# Nixie_Driver.net
KiCad netlist of a schematic drawn in EAGLE
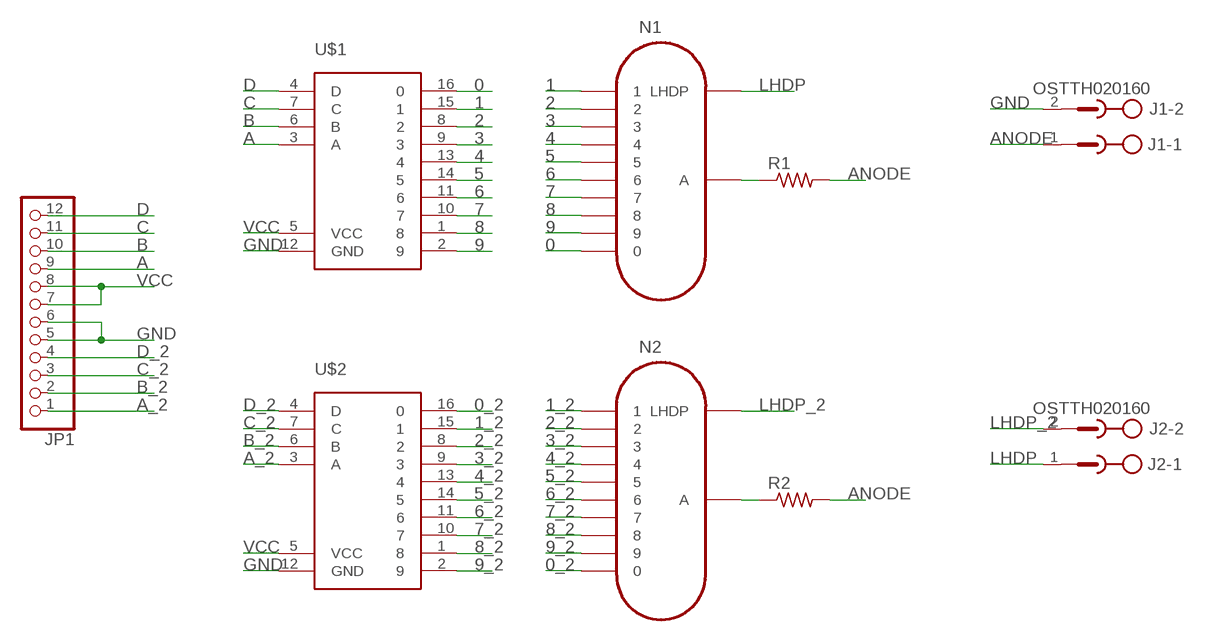
[diagram p0: schematic, sheet 1]

(export (version "E")
  (design (tool "Eeschema 10.0.6"))
  (components
    (comp (ref "J1")
      (value "OSTTH020160")
      (footprint "eagle-import:EDSTL130-02")
      (libsource (lib "eagle-import") (part "OSTTH020160"))
    )
    (comp (ref "J2")
      (value "OSTTH020160")
      (footprint "eagle-import:EDSTL130-02")
      (libsource (lib "eagle-import") (part "OSTTH020160"))
    )
    (comp (ref "JP1")
      (value "PINHD-1X12-CB")
      (footprint "eagle-import:1X12-CB")
      (libsource (lib "eagle-import") (part "PINHD-1X12-CB"))
    )
    (comp (ref "N1")
      (value "IN-12B")
      (footprint "eagle-import:IN-12")
      (libsource (lib "eagle-import") (part "IN-12B"))
    )
    (comp (ref "N2")
      (value "IN-12B")
      (footprint "eagle-import:IN-12")
      (libsource (lib "eagle-import") (part "IN-12B"))
    )
    (comp (ref "R1")
      (value "R-US_0204/7")
      (footprint "eagle-import:0204_7")
      (libsource (lib "eagle-import") (part "R-US_0204/7"))
    )
    (comp (ref "R2")
      (value "R-US_0204/7")
      (footprint "eagle-import:0204_7")
      (libsource (lib "eagle-import") (part "R-US_0204/7"))
    )
    (comp (ref "U$1")
      (value "K155ID1")
      (footprint "eagle-import:DIL16-KIT")
      (libsource (lib "eagle-import") (part "K155ID1"))
    )
    (comp (ref "U$2")
      (value "K155ID1")
      (footprint "eagle-import:DIL16-KIT")
      (libsource (lib "eagle-import") (part "K155ID1"))
    )
  )
  (nets
    (net (code "1") (name "/0") (class "Default")
      (node (ref "N1") (pin "0") (pinfunction "0_0") (pintype "bidirectional"))
      (node (ref "U$1") (pin "16") (pinfunction "0_16") (pintype "bidirectional"))
    )
    (net (code "2") (name "/0_2") (class "Default")
      (node (ref "N2") (pin "0") (pinfunction "0_0") (pintype "bidirectional"))
      (node (ref "U$2") (pin "16") (pinfunction "0_16") (pintype "bidirectional"))
    )
    (net (code "3") (name "/1") (class "Default")
      (node (ref "N1") (pin "1") (pinfunction "1_1") (pintype "bidirectional"))
      (node (ref "U$1") (pin "15") (pinfunction "1_15") (pintype "bidirectional"))
    )
    (net (code "4") (name "/1_2") (class "Default")
      (node (ref "N2") (pin "1") (pinfunction "1_1") (pintype "bidirectional"))
      (node (ref "U$2") (pin "15") (pinfunction "1_15") (pintype "bidirectional"))
    )
    (net (code "5") (name "/2") (class "Default")
      (node (ref "N1") (pin "2") (pinfunction "2_2") (pintype "bidirectional"))
      (node (ref "U$1") (pin "8") (pinfunction "2_8") (pintype "bidirectional"))
    )
    (net (code "6") (name "/2_2") (class "Default")
      (node (ref "N2") (pin "2") (pinfunction "2_2") (pintype "bidirectional"))
      (node (ref "U$2") (pin "8") (pinfunction "2_8") (pintype "bidirectional"))
    )
    (net (code "7") (name "/3") (class "Default")
      (node (ref "N1") (pin "3") (pinfunction "3_3") (pintype "bidirectional"))
      (node (ref "U$1") (pin "9") (pinfunction "3_9") (pintype "bidirectional"))
    )
    (net (code "8") (name "/3_2") (class "Default")
      (node (ref "N2") (pin "3") (pinfunction "3_3") (pintype "bidirectional"))
      (node (ref "U$2") (pin "9") (pinfunction "3_9") (pintype "bidirectional"))
    )
    (net (code "9") (name "/4") (class "Default")
      (node (ref "N1") (pin "4") (pinfunction "4_4") (pintype "bidirectional"))
      (node (ref "U$1") (pin "13") (pinfunction "4_13") (pintype "bidirectional"))
    )
    (net (code "10") (name "/4_2") (class "Default")
      (node (ref "N2") (pin "4") (pinfunction "4_4") (pintype "bidirectional"))
      (node (ref "U$2") (pin "13") (pinfunction "4_13") (pintype "bidirectional"))
    )
    (net (code "11") (name "/5") (class "Default")
      (node (ref "N1") (pin "5") (pinfunction "5_5") (pintype "bidirectional"))
      (node (ref "U$1") (pin "14") (pinfunction "5_14") (pintype "bidirectional"))
    )
    (net (code "12") (name "/5_2") (class "Default")
      (node (ref "N2") (pin "5") (pinfunction "5_5") (pintype "bidirectional"))
      (node (ref "U$2") (pin "14") (pinfunction "5_14") (pintype "bidirectional"))
    )
    (net (code "13") (name "/6") (class "Default")
      (node (ref "N1") (pin "6") (pinfunction "6_6") (pintype "bidirectional"))
      (node (ref "U$1") (pin "11") (pinfunction "6_11") (pintype "bidirectional"))
    )
    (net (code "14") (name "/6_2") (class "Default")
      (node (ref "N2") (pin "6") (pinfunction "6_6") (pintype "bidirectional"))
      (node (ref "U$2") (pin "11") (pinfunction "6_11") (pintype "bidirectional"))
    )
    (net (code "15") (name "/7") (class "Default")
      (node (ref "N1") (pin "7") (pinfunction "7_7") (pintype "bidirectional"))
      (node (ref "U$1") (pin "10") (pinfunction "7_10") (pintype "bidirectional"))
    )
    (net (code "16") (name "/7_2") (class "Default")
      (node (ref "N2") (pin "7") (pinfunction "7_7") (pintype "bidirectional"))
      (node (ref "U$2") (pin "10") (pinfunction "7_10") (pintype "bidirectional"))
    )
    (net (code "17") (name "/8") (class "Default")
      (node (ref "N1") (pin "8") (pinfunction "8_8") (pintype "bidirectional"))
      (node (ref "U$1") (pin "1") (pinfunction "8_1") (pintype "bidirectional"))
    )
    (net (code "18") (name "/8_2") (class "Default")
      (node (ref "N2") (pin "8") (pinfunction "8_8") (pintype "bidirectional"))
      (node (ref "U$2") (pin "1") (pinfunction "8_1") (pintype "bidirectional"))
    )
    (net (code "19") (name "/9") (class "Default")
      (node (ref "N1") (pin "9") (pinfunction "9_9") (pintype "bidirectional"))
      (node (ref "U$1") (pin "2") (pinfunction "9_2") (pintype "bidirectional"))
    )
    (net (code "20") (name "/9_2") (class "Default")
      (node (ref "N2") (pin "9") (pinfunction "9_9") (pintype "bidirectional"))
      (node (ref "U$2") (pin "2") (pinfunction "9_2") (pintype "bidirectional"))
    )
    (net (code "21") (name "/A") (class "Default")
      (node (ref "JP1") (pin "9") (pinfunction "9_9") (pintype "passive"))
      (node (ref "U$1") (pin "3") (pinfunction "A_3") (pintype "input"))
    )
    (net (code "22") (name "/ANODE") (class "Default")
      (node (ref "J1") (pin "1") (pinfunction "SK_1") (pintype "passive"))
      (node (ref "R1") (pin "2") (pinfunction "2_2") (pintype "passive"))
      (node (ref "R2") (pin "2") (pinfunction "2_2") (pintype "passive"))
    )
    (net (code "23") (name "/A_2") (class "Default")
      (node (ref "JP1") (pin "1") (pinfunction "1_1") (pintype "passive"))
      (node (ref "U$2") (pin "3") (pinfunction "A_3") (pintype "input"))
    )
    (net (code "24") (name "/B") (class "Default")
      (node (ref "JP1") (pin "10") (pinfunction "10_10") (pintype "passive"))
      (node (ref "U$1") (pin "6") (pinfunction "B_6") (pintype "input"))
    )
    (net (code "25") (name "/B_2") (class "Default")
      (node (ref "JP1") (pin "2") (pinfunction "2_2") (pintype "passive"))
      (node (ref "U$2") (pin "6") (pinfunction "B_6") (pintype "input"))
    )
    (net (code "26") (name "/C") (class "Default")
      (node (ref "JP1") (pin "11") (pinfunction "11_11") (pintype "passive"))
      (node (ref "U$1") (pin "7") (pinfunction "C_7") (pintype "input"))
    )
    (net (code "27") (name "/C_2") (class "Default")
      (node (ref "JP1") (pin "3") (pinfunction "3_3") (pintype "passive"))
      (node (ref "U$2") (pin "7") (pinfunction "C_7") (pintype "input"))
    )
    (net (code "28") (name "/D") (class "Default")
      (node (ref "JP1") (pin "12") (pinfunction "12_12") (pintype "passive"))
      (node (ref "U$1") (pin "4") (pinfunction "D_4") (pintype "input"))
    )
    (net (code "29") (name "/D_2") (class "Default")
      (node (ref "JP1") (pin "4") (pinfunction "4_4") (pintype "passive"))
      (node (ref "U$2") (pin "4") (pinfunction "D_4") (pintype "input"))
    )
    (net (code "30") (name "/GND") (class "Default")
      (node (ref "J1") (pin "2") (pinfunction "SK_2") (pintype "passive"))
      (node (ref "JP1") (pin "5") (pinfunction "5_5") (pintype "passive"))
      (node (ref "JP1") (pin "6") (pinfunction "6_6") (pintype "passive"))
      (node (ref "U$1") (pin "12") (pinfunction "GND_12") (pintype "bidirectional"))
      (node (ref "U$2") (pin "12") (pinfunction "GND_12") (pintype "bidirectional"))
    )
    (net (code "31") (name "/LHDP") (class "Default")
      (node (ref "J2") (pin "1") (pinfunction "SK_1") (pintype "passive"))
      (node (ref "N1") (pin "LHDP") (pinfunction "LHDP_LHDP") (pintype "bidirectional"))
    )
    (net (code "32") (name "/LHDP_2") (class "Default")
      (node (ref "J2") (pin "2") (pinfunction "SK_2") (pintype "passive"))
      (node (ref "N2") (pin "LHDP") (pinfunction "LHDP_LHDP") (pintype "bidirectional"))
    )
    (net (code "33") (name "/VCC") (class "Default")
      (node (ref "JP1") (pin "7") (pinfunction "7_7") (pintype "passive"))
      (node (ref "JP1") (pin "8") (pinfunction "8_8") (pintype "passive"))
      (node (ref "U$1") (pin "5") (pinfunction "VCC_5") (pintype "bidirectional"))
      (node (ref "U$2") (pin "5") (pinfunction "VCC_5") (pintype "bidirectional"))
    )
    (net (code "34") (name "Net-(N1-PadA)") (class "Default")
      (node (ref "N1") (pin "A") (pinfunction "A_A") (pintype "bidirectional"))
      (node (ref "R1") (pin "1") (pinfunction "1_1") (pintype "passive"))
    )
    (net (code "35") (name "Net-(N2-PadA)") (class "Default")
      (node (ref "N2") (pin "A") (pinfunction "A_A") (pintype "bidirectional"))
      (node (ref "R2") (pin "1") (pinfunction "1_1") (pintype "passive"))
    )
  )
)
